# meduza01.net
KiCad netlist of a schematic drawn in EAGLE
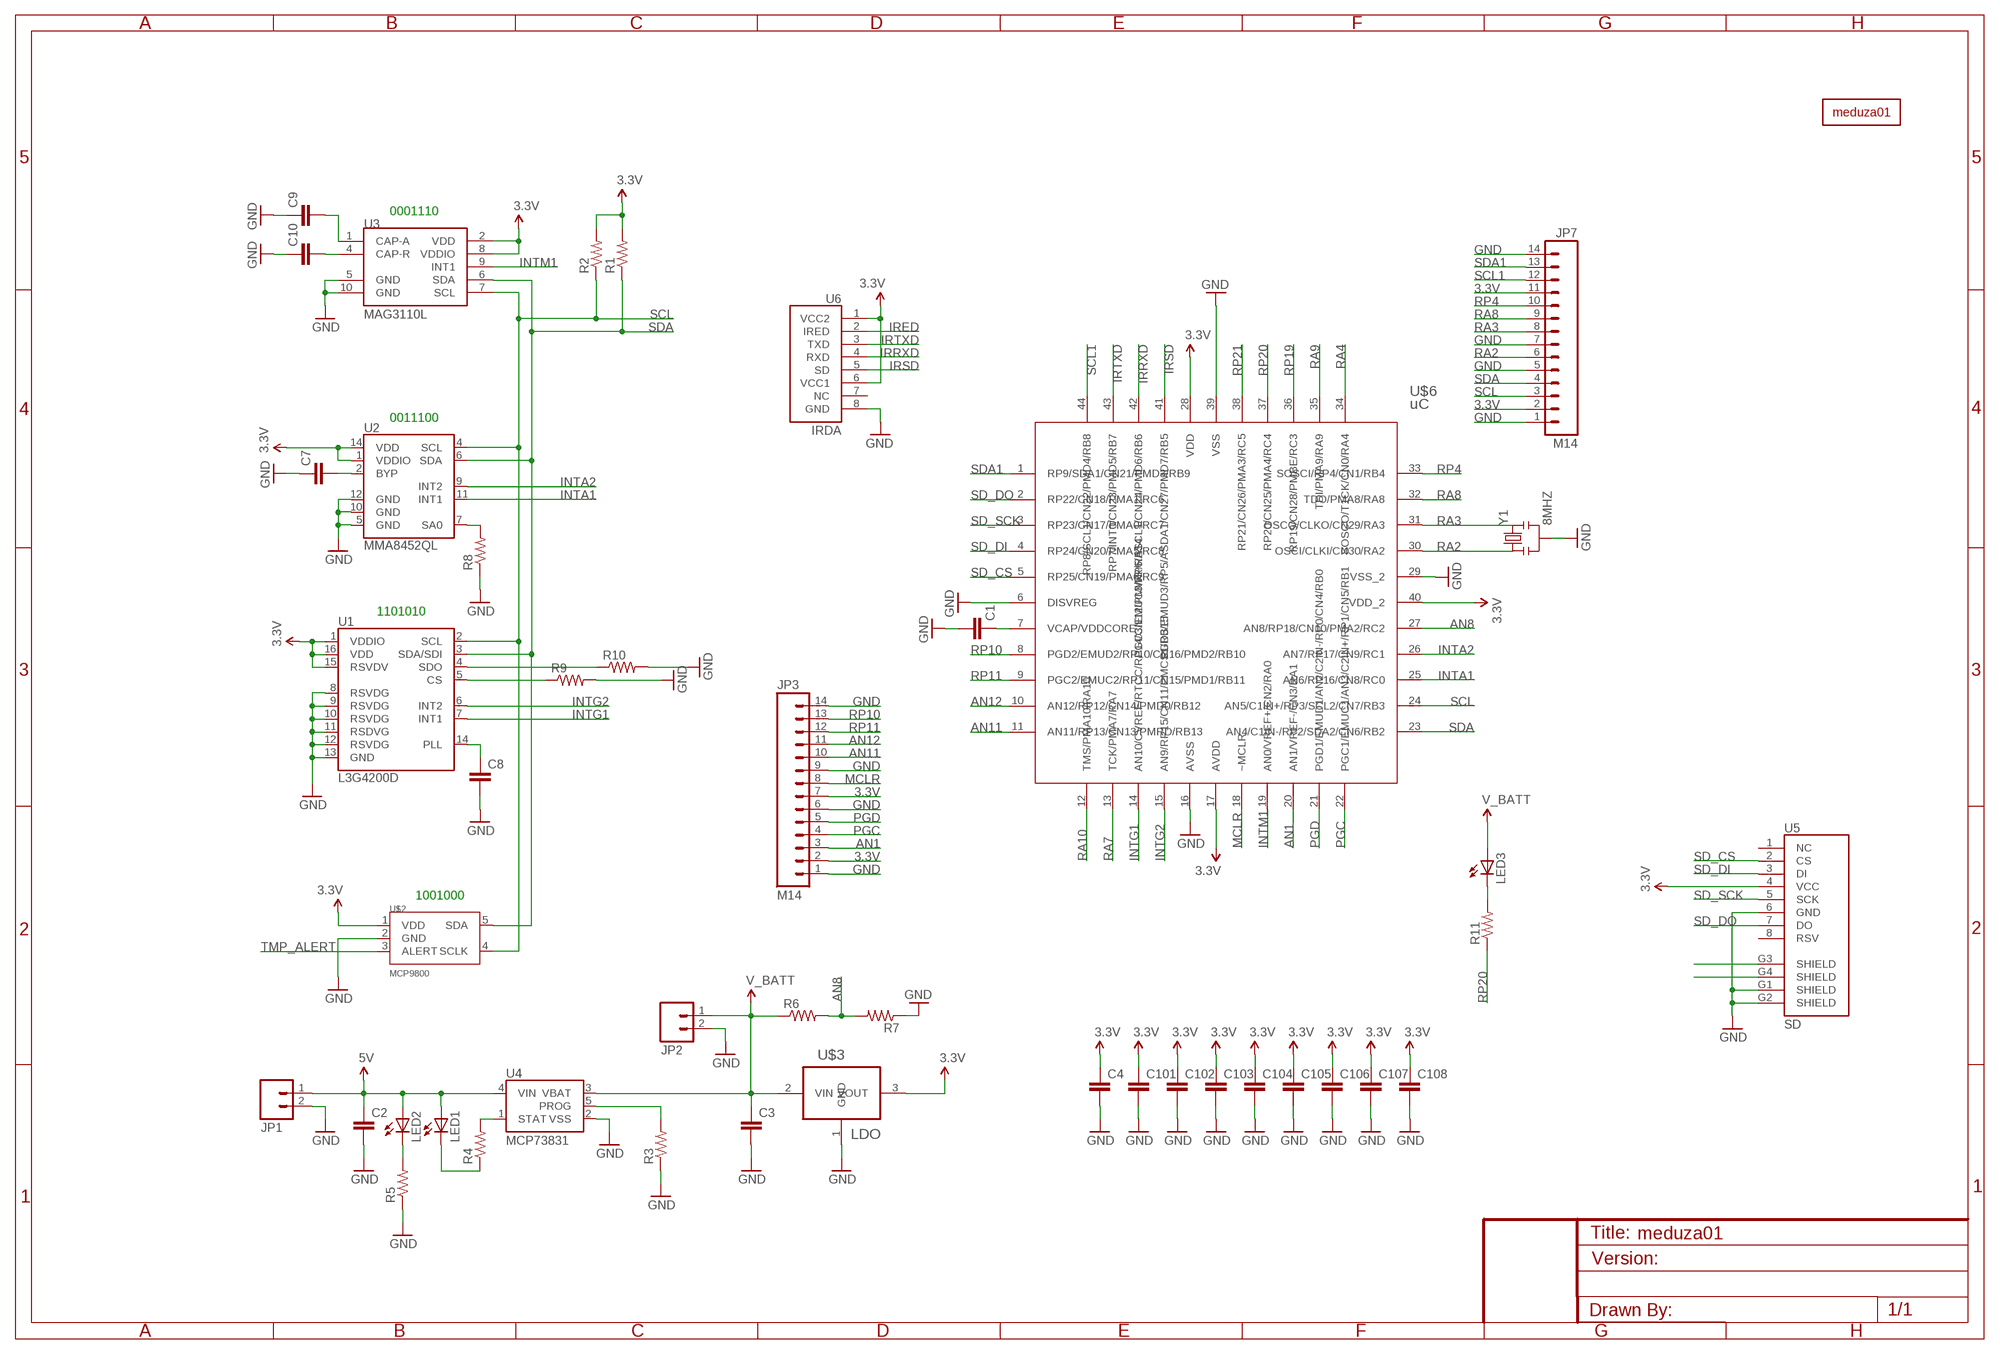
[diagram p0: schematic, sheet 1]

(export (version "E")
  (design (tool "Eeschema 10.0.6"))
  (components
    (comp (ref "C1")
      (value "CAP0603-CAP")
      (footprint "eagle-import:0603-CAP")
      (libsource (lib "eagle-import") (part "CAP0603-CAP"))
    )
    (comp (ref "C2")
      (value "CAP0805")
      (footprint "eagle-import:0805")
      (libsource (lib "eagle-import") (part "SparkFun-Passives_CAP0805"))
    )
    (comp (ref "C3")
      (value "CAP0805")
      (footprint "eagle-import:0805")
      (libsource (lib "eagle-import") (part "SparkFun-Passives_CAP0805"))
    )
    (comp (ref "C4")
      (value "CAP0805")
      (footprint "eagle-import:0805")
      (libsource (lib "eagle-import") (part "SparkFun-Passives_CAP0805"))
    )
    (comp (ref "C7")
      (value "CAP0603-CAP")
      (footprint "eagle-import:0603-CAP")
      (libsource (lib "eagle-import") (part "CAP0603-CAP"))
    )
    (comp (ref "C8")
      (value "CAP0603-CAP")
      (footprint "eagle-import:0603-CAP")
      (libsource (lib "eagle-import") (part "CAP0603-CAP"))
    )
    (comp (ref "C9")
      (value "CAP0603-CAP")
      (footprint "eagle-import:0603-CAP")
      (libsource (lib "eagle-import") (part "CAP0603-CAP"))
    )
    (comp (ref "C10")
      (value "CAP0603-CAP")
      (footprint "eagle-import:0603-CAP")
      (libsource (lib "eagle-import") (part "CAP0603-CAP"))
    )
    (comp (ref "C101")
      (value "CAP0603-CAP")
      (footprint "eagle-import:0603-CAP")
      (libsource (lib "eagle-import") (part "CAP0603-CAP"))
    )
    (comp (ref "C102")
      (value "CAP0603-CAP")
      (footprint "eagle-import:0603-CAP")
      (libsource (lib "eagle-import") (part "CAP0603-CAP"))
    )
    (comp (ref "C103")
      (value "CAP0603-CAP")
      (footprint "eagle-import:0603-CAP")
      (libsource (lib "eagle-import") (part "CAP0603-CAP"))
    )
    (comp (ref "C104")
      (value "CAP0603-CAP")
      (footprint "eagle-import:0603-CAP")
      (libsource (lib "eagle-import") (part "CAP0603-CAP"))
    )
    (comp (ref "C105")
      (value "CAP0603-CAP")
      (footprint "eagle-import:0603-CAP")
      (libsource (lib "eagle-import") (part "CAP0603-CAP"))
    )
    (comp (ref "C106")
      (value "CAP0603-CAP")
      (footprint "eagle-import:0603-CAP")
      (libsource (lib "eagle-import") (part "CAP0603-CAP"))
    )
    (comp (ref "C107")
      (value "CAP0603-CAP")
      (footprint "eagle-import:0603-CAP")
      (libsource (lib "eagle-import") (part "CAP0603-CAP"))
    )
    (comp (ref "C108")
      (value "CAP0603-CAP")
      (footprint "eagle-import:0603-CAP")
      (libsource (lib "eagle-import") (part "CAP0603-CAP"))
    )
    (comp (ref "JP1")
      (value "M02PTH")
      (footprint "eagle-import:1X02")
      (libsource (lib "eagle-import") (part "M02PTH"))
    )
    (comp (ref "JP2")
      (value "M02PTH")
      (footprint "eagle-import:1X02")
      (libsource (lib "eagle-import") (part "M02PTH"))
    )
    (comp (ref "JP3")
      (value "M14")
      (footprint "eagle-import:1X14")
      (libsource (lib "eagle-import") (part "M14"))
    )
    (comp (ref "JP7")
      (value "M14")
      (footprint "eagle-import:1X14")
      (libsource (lib "eagle-import") (part "M14"))
    )
    (comp (ref "LED1")
      (value "LED1206")
      (footprint "eagle-import:LED-1206")
      (libsource (lib "eagle-import") (part "LED1206"))
    )
    (comp (ref "LED2")
      (value "LED1206")
      (footprint "eagle-import:LED-1206")
      (libsource (lib "eagle-import") (part "LED1206"))
    )
    (comp (ref "LED3")
      (value "LED1206")
      (footprint "eagle-import:LED-1206")
      (libsource (lib "eagle-import") (part "LED1206"))
    )
    (comp (ref "R1")
      (value "RESISTOR0603-RES")
      (footprint "eagle-import:0603-RES")
      (libsource (lib "eagle-import") (part "RESISTOR0603-RES"))
    )
    (comp (ref "R2")
      (value "RESISTOR0603-RES")
      (footprint "eagle-import:0603-RES")
      (libsource (lib "eagle-import") (part "RESISTOR0603-RES"))
    )
    (comp (ref "R3")
      (value "RESISTOR0603-RES")
      (footprint "eagle-import:0603-RES")
      (libsource (lib "eagle-import") (part "SparkFun-Resistors_RESISTOR0603-RES"))
    )
    (comp (ref "R4")
      (value "RESISTOR0603-RES")
      (footprint "eagle-import:0603-RES")
      (libsource (lib "eagle-import") (part "SparkFun-Resistors_RESISTOR0603-RES"))
    )
    (comp (ref "R5")
      (value "RESISTOR0603-RES")
      (footprint "eagle-import:0603-RES")
      (libsource (lib "eagle-import") (part "SparkFun-Resistors_RESISTOR0603-RES"))
    )
    (comp (ref "R6")
      (value "RESISTOR0603-RES")
      (footprint "eagle-import:0603-RES")
      (libsource (lib "eagle-import") (part "SparkFun-Resistors_RESISTOR0603-RES"))
    )
    (comp (ref "R7")
      (value "RESISTOR0603-RES")
      (footprint "eagle-import:0603-RES")
      (libsource (lib "eagle-import") (part "SparkFun-Resistors_RESISTOR0603-RES"))
    )
    (comp (ref "R8")
      (value "RESISTOR0603-RES")
      (footprint "eagle-import:0603-RES")
      (libsource (lib "eagle-import") (part "RESISTOR0603-RES"))
    )
    (comp (ref "R9")
      (value "RESISTOR0603-RES")
      (footprint "eagle-import:0603-RES")
      (libsource (lib "eagle-import") (part "RESISTOR0603-RES"))
    )
    (comp (ref "R10")
      (value "RESISTOR0603-RES")
      (footprint "eagle-import:0603-RES")
      (libsource (lib "eagle-import") (part "RESISTOR0603-RES"))
    )
    (comp (ref "R11")
      (value "RESISTOR0603-RES")
      (footprint "eagle-import:0603-RES")
      (libsource (lib "eagle-import") (part "SparkFun-Resistors_RESISTOR0603-RES"))
    )
    (comp (ref "U$1")
      (value "MEDUZA01")
      (footprint "eagle-import:MEDUZA01")
      (libsource (lib "eagle-import") (part "MEDUZA01"))
    )
    (comp (ref "U$2")
      (value "MCP9800")
      (footprint "eagle-import:SOT23-5")
      (libsource (lib "eagle-import") (part "MCP9800"))
    )
    (comp (ref "U$3")
      (value "LDO")
      (footprint "eagle-import:SOT89R")
      (libsource (lib "eagle-import") (part "MCP1700T-3302E/TTSOT89MCP1700-3N"))
    )
    (comp (ref "U$6")
      (value "uC")
      (footprint "eagle-import:QFP80P1200X1200X120-44N")
      (fields (field (name "MPN") "PIC24FJ64GA004-I/PT"))
      (libsource (lib "eagle-import") (part "PIC24FJ64GA004"))
    )
    (comp (ref "U1")
      (value "L3G4200D")
      (footprint "eagle-import:LGA16-4X4")
      (libsource (lib "eagle-import") (part "L3G4200D"))
    )
    (comp (ref "U2")
      (value "MMA8452QL")
      (footprint "eagle-import:QFN-16_0.5MM-EXTRA")
      (libsource (lib "eagle-import") (part "MMA8452QL"))
    )
    (comp (ref "U3")
      (value "MAG3110L")
      (footprint "eagle-import:DFN-10-EXTRA")
      (libsource (lib "eagle-import") (part "MAG3110L"))
    )
    (comp (ref "U4")
      (value "MCP73831")
      (footprint "eagle-import:SOT23-5")
      (libsource (lib "eagle-import") (part "MCP73831"))
    )
    (comp (ref "U5")
      (value "SD")
      (footprint "eagle-import:MOLEX-SD-47309")
      (libsource (lib "eagle-import") (part "USD-SOCKETMOLEX47309"))
    )
    (comp (ref "U6")
      (value "IRDA")
      (footprint "eagle-import:TFDU6300")
      (libsource (lib "eagle-import") (part "TFDU6300TFDU6300"))
    )
    (comp (ref "Y1")
      (value "8MHZ")
      (footprint "eagle-import:RESONATOR-SMD")
      (libsource (lib "eagle-import") (part "RESONATOR8MHZ"))
    )
  )
  (nets
    (net (code "1") (name "/AN1") (class "Default")
      (node (ref "JP3") (pin "3") (pinfunction "3_3") (pintype "passive"))
      (node (ref "U$6") (pin "20") (pinfunction "AN1/VREF-/CN3/RA1_20") (pintype "bidirectional"))
    )
    (net (code "2") (name "/AN8") (class "Default")
      (node (ref "R6") (pin "2") (pinfunction "2_2") (pintype "passive"))
      (node (ref "R7") (pin "2") (pinfunction "2_2") (pintype "passive"))
      (node (ref "U$6") (pin "27") (pinfunction "AN8/RP18/CN10/PMA2/RC2_27") (pintype "bidirectional"))
    )
    (net (code "3") (name "/AN11") (class "Default")
      (node (ref "JP3") (pin "10") (pinfunction "10_10") (pintype "passive"))
      (node (ref "U$6") (pin "11") (pinfunction "AN11/RP13/CN13/PMRD/RB13_11") (pintype "bidirectional"))
    )
    (net (code "4") (name "/AN12") (class "Default")
      (node (ref "JP3") (pin "11") (pinfunction "11_11") (pintype "passive"))
      (node (ref "U$6") (pin "10") (pinfunction "AN12/RP12/CN14/PMD0/RB12_10") (pintype "bidirectional"))
    )
    (net (code "5") (name "/INTA1") (class "Default")
      (node (ref "U$6") (pin "25") (pinfunction "AN6/RP16/CN8/RC0_25") (pintype "bidirectional"))
      (node (ref "U2") (pin "11") (pinfunction "INT1_11") (pintype "bidirectional"))
    )
    (net (code "6") (name "/INTA2") (class "Default")
      (node (ref "U$6") (pin "26") (pinfunction "AN7/RP17/CN9/RC1_26") (pintype "bidirectional"))
      (node (ref "U2") (pin "9") (pinfunction "INT2_9") (pintype "bidirectional"))
    )
    (net (code "7") (name "/INTG1") (class "Default")
      (node (ref "U$6") (pin "14") (pinfunction "AN10/CVREF/RTCC/RP14/CN12/PMWR/RB14_14") (pintype "bidirectional"))
      (node (ref "U1") (pin "7") (pinfunction "INT1_7") (pintype "bidirectional"))
    )
    (net (code "8") (name "/INTG2") (class "Default")
      (node (ref "U$6") (pin "15") (pinfunction "AN9/RP15/CN11/PMCS1/RB15_15") (pintype "bidirectional"))
      (node (ref "U1") (pin "6") (pinfunction "INT2_6") (pintype "bidirectional"))
    )
    (net (code "9") (name "/INTM1") (class "Default")
      (node (ref "U$6") (pin "19") (pinfunction "AN0/VREF+/CN2/RA0_19") (pintype "bidirectional"))
      (node (ref "U3") (pin "9") (pinfunction "INT1_9") (pintype "bidirectional"))
    )
    (net (code "10") (name "/IRED") (class "Default")
      (node (ref "U6") (pin "2") (pinfunction "IRED_2") (pintype "bidirectional"))
    )
    (net (code "11") (name "/IRRXD") (class "Default")
      (node (ref "U$6") (pin "42") (pinfunction "PGC3/EMUC3/RP6/ASCL1/CN24/PMD6/RB6_42") (pintype "bidirectional"))
      (node (ref "U6") (pin "4") (pinfunction "RXD_4") (pintype "bidirectional"))
    )
    (net (code "12") (name "/IRSD") (class "Default")
      (node (ref "U$6") (pin "41") (pinfunction "PGD3/EMUD3/RP5/ASDA1/CN27/PMD7/RB5_41") (pintype "bidirectional"))
      (node (ref "U6") (pin "5") (pinfunction "SD_5") (pintype "bidirectional"))
    )
    (net (code "13") (name "/IRTXD") (class "Default")
      (node (ref "U$6") (pin "43") (pinfunction "RP7/INT0/CN23/PMD5/RB7_43") (pintype "bidirectional"))
      (node (ref "U6") (pin "3") (pinfunction "TXD_3") (pintype "bidirectional"))
    )
    (net (code "14") (name "/MCLR") (class "Default")
      (node (ref "JP3") (pin "8") (pinfunction "8_8") (pintype "passive"))
      (node (ref "U$6") (pin "18") (pinfunction "~{MCLR}_18") (pintype "bidirectional"))
    )
    (net (code "15") (name "/PGC") (class "Default")
      (node (ref "JP3") (pin "4") (pinfunction "4_4") (pintype "passive"))
      (node (ref "U$6") (pin "22") (pinfunction "PGC1/EMUC1/AN3/C2IN+/RP1/CN5/RB1_22") (pintype "bidirectional"))
    )
    (net (code "16") (name "/PGD") (class "Default")
      (node (ref "JP3") (pin "5") (pinfunction "5_5") (pintype "passive"))
      (node (ref "U$6") (pin "21") (pinfunction "PGD1/EMUD1/AN2/C2IN-/RP0/CN4/RB0_21") (pintype "bidirectional"))
    )
    (net (code "17") (name "/RA2") (class "Default")
      (node (ref "JP7") (pin "6") (pinfunction "6_6") (pintype "passive"))
      (node (ref "U$6") (pin "30") (pinfunction "OSCI/CLKI/CN30/RA2_30") (pintype "bidirectional"))
      (node (ref "Y1") (pin "1") (pinfunction "1_1") (pintype "passive"))
    )
    (net (code "18") (name "/RA3") (class "Default")
      (node (ref "JP7") (pin "8") (pinfunction "8_8") (pintype "passive"))
      (node (ref "U$6") (pin "31") (pinfunction "OSCO/CLKO/CN29/RA3_31") (pintype "bidirectional"))
      (node (ref "Y1") (pin "3") (pinfunction "3_3") (pintype "passive"))
    )
    (net (code "19") (name "/RA4") (class "Default")
      (node (ref "U$6") (pin "34") (pinfunction "SOSCO/T1CK/CN0/RA4_34") (pintype "bidirectional"))
    )
    (net (code "20") (name "/RA7") (class "Default")
      (node (ref "U$6") (pin "13") (pinfunction "TCK/PMA7/RA7_13") (pintype "bidirectional"))
    )
    (net (code "21") (name "/RA8") (class "Default")
      (node (ref "JP7") (pin "9") (pinfunction "9_9") (pintype "passive"))
      (node (ref "U$6") (pin "32") (pinfunction "TDO/PMA8/RA8_32") (pintype "bidirectional"))
    )
    (net (code "22") (name "/RA9") (class "Default")
      (node (ref "U$6") (pin "35") (pinfunction "TDI/PMA9/RA9_35") (pintype "bidirectional"))
    )
    (net (code "23") (name "/RA10") (class "Default")
      (node (ref "U$6") (pin "12") (pinfunction "TMS/PMA10/RA10_12") (pintype "bidirectional"))
    )
    (net (code "24") (name "/RP4") (class "Default")
      (node (ref "JP7") (pin "10") (pinfunction "10_10") (pintype "passive"))
      (node (ref "U$6") (pin "33") (pinfunction "SOSCI/RP4/CN1/RB4_33") (pintype "bidirectional"))
    )
    (net (code "25") (name "/RP10") (class "Default")
      (node (ref "JP3") (pin "13") (pinfunction "13_13") (pintype "passive"))
      (node (ref "U$6") (pin "8") (pinfunction "PGD2/EMUD2/RP10/CN16/PMD2/RB10_8") (pintype "bidirectional"))
    )
    (net (code "26") (name "/RP11") (class "Default")
      (node (ref "JP3") (pin "12") (pinfunction "12_12") (pintype "passive"))
      (node (ref "U$6") (pin "9") (pinfunction "PGC2/EMUC2/RP11/CN15/PMD1/RB11_9") (pintype "bidirectional"))
    )
    (net (code "27") (name "/RP19") (class "Default")
      (node (ref "U$6") (pin "36") (pinfunction "RP19/CN28/PMBE/RC3_36") (pintype "bidirectional"))
    )
    (net (code "28") (name "/RP20") (class "Default")
      (node (ref "R11") (pin "1") (pinfunction "1_1") (pintype "passive"))
      (node (ref "U$6") (pin "37") (pinfunction "RP20/CN25/PMA4/RC4_37") (pintype "bidirectional"))
    )
    (net (code "29") (name "/RP21") (class "Default")
      (node (ref "U$6") (pin "38") (pinfunction "RP21/CN26/PMA3/RC5_38") (pintype "bidirectional"))
    )
    (net (code "30") (name "/SCL") (class "Default")
      (node (ref "JP7") (pin "3") (pinfunction "3_3") (pintype "passive"))
      (node (ref "R2") (pin "1") (pinfunction "1_1") (pintype "passive"))
      (node (ref "U$2") (pin "4") (pinfunction "SCLK_4") (pintype "input"))
      (node (ref "U$6") (pin "24") (pinfunction "AN5/C1IN+/RP3/SCL2/CN7/RB3_24") (pintype "bidirectional"))
      (node (ref "U1") (pin "2") (pinfunction "SCL_2") (pintype "bidirectional"))
      (node (ref "U2") (pin "4") (pinfunction "SCL_4") (pintype "bidirectional"))
      (node (ref "U3") (pin "7") (pinfunction "SCL_7") (pintype "bidirectional"))
    )
    (net (code "31") (name "/SCL1") (class "Default")
      (node (ref "JP7") (pin "12") (pinfunction "12_12") (pintype "passive"))
      (node (ref "U$6") (pin "44") (pinfunction "RP8/SCL1/CN22/PMD4/RB8_44") (pintype "bidirectional"))
    )
    (net (code "32") (name "/SDA") (class "Default")
      (node (ref "JP7") (pin "4") (pinfunction "4_4") (pintype "passive"))
      (node (ref "R1") (pin "1") (pinfunction "1_1") (pintype "passive"))
      (node (ref "U$2") (pin "5") (pinfunction "SDA_5") (pintype "bidirectional"))
      (node (ref "U$6") (pin "23") (pinfunction "AN4/C1IN-/RP2/SDA2/CN6/RB2_23") (pintype "bidirectional"))
      (node (ref "U1") (pin "3") (pinfunction "SDA/SDI_3") (pintype "bidirectional"))
      (node (ref "U2") (pin "6") (pinfunction "SDA_6") (pintype "bidirectional"))
      (node (ref "U3") (pin "6") (pinfunction "SDA_6") (pintype "bidirectional"))
    )
    (net (code "33") (name "/SDA1") (class "Default")
      (node (ref "JP7") (pin "13") (pinfunction "13_13") (pintype "passive"))
      (node (ref "U$6") (pin "1") (pinfunction "RP9/SDA1/CN21/PMD3/RB9_1") (pintype "bidirectional"))
    )
    (net (code "34") (name "/SD_CS") (class "Default")
      (node (ref "U$6") (pin "5") (pinfunction "RP25/CN19/PMA6/RC9_5") (pintype "bidirectional"))
      (node (ref "U5") (pin "2") (pinfunction "CS_2") (pintype "bidirectional"))
    )
    (net (code "35") (name "/SD_DI") (class "Default")
      (node (ref "U$6") (pin "4") (pinfunction "RP24/CN20/PMA5/RC8_4") (pintype "bidirectional"))
      (node (ref "U5") (pin "3") (pinfunction "DI_3") (pintype "bidirectional"))
    )
    (net (code "36") (name "/SD_DO") (class "Default")
      (node (ref "U$6") (pin "2") (pinfunction "RP22/CN18/PMA1/RC6_2") (pintype "bidirectional"))
      (node (ref "U5") (pin "7") (pinfunction "DO_7") (pintype "bidirectional"))
    )
    (net (code "37") (name "/SD_SCK") (class "Default")
      (node (ref "U$6") (pin "3") (pinfunction "RP23/CN17/PMA0/RC7_3") (pintype "bidirectional"))
      (node (ref "U5") (pin "5") (pinfunction "SCK_5") (pintype "bidirectional"))
    )
    (net (code "38") (name "/TMP_ALERT") (class "Default")
      (node (ref "U$2") (pin "3") (pinfunction "ALERT_3") (pintype "output"))
    )
    (net (code "39") (name "3.3V") (class "Default")
      (node (ref "C101") (pin "1") (pinfunction "1_1") (pintype "passive"))
      (node (ref "C102") (pin "1") (pinfunction "1_1") (pintype "passive"))
      (node (ref "C103") (pin "1") (pinfunction "1_1") (pintype "passive"))
      (node (ref "C104") (pin "1") (pinfunction "1_1") (pintype "passive"))
      (node (ref "C105") (pin "1") (pinfunction "1_1") (pintype "passive"))
      (node (ref "C106") (pin "1") (pinfunction "1_1") (pintype "passive"))
      (node (ref "C107") (pin "1") (pinfunction "1_1") (pintype "passive"))
      (node (ref "C108") (pin "1") (pinfunction "1_1") (pintype "passive"))
      (node (ref "C4") (pin "1") (pinfunction "1_1") (pintype "passive"))
      (node (ref "JP3") (pin "2") (pinfunction "2_2") (pintype "passive"))
      (node (ref "JP3") (pin "7") (pinfunction "7_7") (pintype "passive"))
      (node (ref "JP7") (pin "11") (pinfunction "11_11") (pintype "passive"))
      (node (ref "JP7") (pin "2") (pinfunction "2_2") (pintype "passive"))
      (node (ref "R1") (pin "2") (pinfunction "2_2") (pintype "passive"))
      (node (ref "R2") (pin "2") (pinfunction "2_2") (pintype "passive"))
      (node (ref "U$2") (pin "1") (pinfunction "VDD_1") (pintype "power_in"))
      (node (ref "U$3") (pin "3") (pinfunction "VOUT_3") (pintype "output"))
      (node (ref "U$6") (pin "17") (pinfunction "AVDD_17") (pintype "power_in"))
      (node (ref "U$6") (pin "28") (pinfunction "VDD_28") (pintype "power_in"))
      (node (ref "U$6") (pin "40") (pinfunction "VDD_2_40") (pintype "power_in"))
      (node (ref "U1") (pin "1") (pinfunction "VDDIO_1") (pintype "bidirectional"))
      (node (ref "U1") (pin "15") (pinfunction "RSVDV_15") (pintype "bidirectional"))
      (node (ref "U1") (pin "16") (pinfunction "VDD_16") (pintype "bidirectional"))
      (node (ref "U2") (pin "1") (pinfunction "VDDIO_1") (pintype "bidirectional"))
      (node (ref "U2") (pin "14") (pinfunction "VDD_14") (pintype "bidirectional"))
      (node (ref "U3") (pin "2") (pinfunction "VDD_2") (pintype "bidirectional"))
      (node (ref "U3") (pin "8") (pinfunction "VDDIO_8") (pintype "bidirectional"))
      (node (ref "U5") (pin "4") (pinfunction "VCC_4") (pintype "bidirectional"))
      (node (ref "U6") (pin "1") (pinfunction "VCC2_1") (pintype "bidirectional"))
      (node (ref "U6") (pin "6") (pinfunction "VCC1_6") (pintype "bidirectional"))
    )
    (net (code "40") (name "5V") (class "Default")
      (node (ref "C2") (pin "1") (pinfunction "1_1") (pintype "passive"))
      (node (ref "JP1") (pin "1") (pinfunction "1_1") (pintype "passive"))
      (node (ref "LED1") (pin "A") (pinfunction "A_A") (pintype "passive"))
      (node (ref "LED2") (pin "A") (pinfunction "A_A") (pintype "passive"))
      (node (ref "U4") (pin "4") (pinfunction "VIN_4") (pintype "power_in"))
    )
    (net (code "41") (name "GND") (class "Default")
      (node (ref "C1") (pin "2") (pinfunction "2_2") (pintype "passive"))
      (node (ref "C10") (pin "1") (pinfunction "1_1") (pintype "passive"))
      (node (ref "C101") (pin "2") (pinfunction "2_2") (pintype "passive"))
      (node (ref "C102") (pin "2") (pinfunction "2_2") (pintype "passive"))
      (node (ref "C103") (pin "2") (pinfunction "2_2") (pintype "passive"))
      (node (ref "C104") (pin "2") (pinfunction "2_2") (pintype "passive"))
      (node (ref "C105") (pin "2") (pinfunction "2_2") (pintype "passive"))
      (node (ref "C106") (pin "2") (pinfunction "2_2") (pintype "passive"))
      (node (ref "C107") (pin "2") (pinfunction "2_2") (pintype "passive"))
      (node (ref "C108") (pin "2") (pinfunction "2_2") (pintype "passive"))
      (node (ref "C2") (pin "2") (pinfunction "2_2") (pintype "passive"))
      (node (ref "C3") (pin "2") (pinfunction "2_2") (pintype "passive"))
      (node (ref "C4") (pin "2") (pinfunction "2_2") (pintype "passive"))
      (node (ref "C7") (pin "1") (pinfunction "1_1") (pintype "passive"))
      (node (ref "C8") (pin "2") (pinfunction "2_2") (pintype "passive"))
      (node (ref "C9") (pin "1") (pinfunction "1_1") (pintype "passive"))
      (node (ref "JP1") (pin "2") (pinfunction "2_2") (pintype "passive"))
      (node (ref "JP2") (pin "2") (pinfunction "2_2") (pintype "passive"))
      (node (ref "JP3") (pin "1") (pinfunction "1_1") (pintype "passive"))
      (node (ref "JP3") (pin "14") (pinfunction "14_14") (pintype "passive"))
      (node (ref "JP3") (pin "6") (pinfunction "6_6") (pintype "passive"))
      (node (ref "JP3") (pin "9") (pinfunction "9_9") (pintype "passive"))
      (node (ref "JP7") (pin "1") (pinfunction "1_1") (pintype "passive"))
      (node (ref "JP7") (pin "14") (pinfunction "14_14") (pintype "passive"))
      (node (ref "JP7") (pin "5") (pinfunction "5_5") (pintype "passive"))
      (node (ref "JP7") (pin "7") (pinfunction "7_7") (pintype "passive"))
      (node (ref "R10") (pin "2") (pinfunction "2_2") (pintype "passive"))
      (node (ref "R3") (pin "1") (pinfunction "1_1") (pintype "passive"))
      (node (ref "R5") (pin "1") (pinfunction "1_1") (pintype "passive"))
      (node (ref "R7") (pin "1") (pinfunction "1_1") (pintype "passive"))
      (node (ref "R8") (pin "1") (pinfunction "1_1") (pintype "passive"))
      (node (ref "R9") (pin "2") (pinfunction "2_2") (pintype "passive"))
      (node (ref "U$2") (pin "2") (pinfunction "GND_2") (pintype "passive"))
      (node (ref "U$3") (pin "1") (pinfunction "GND_1") (pintype "passive"))
      (node (ref "U$6") (pin "16") (pinfunction "AVSS_16") (pintype "power_in"))
      (node (ref "U$6") (pin "29") (pinfunction "VSS_2_29") (pintype "power_in"))
      (node (ref "U$6") (pin "39") (pinfunction "VSS_39") (pintype "power_in"))
      (node (ref "U$6") (pin "6") (pinfunction "DISVREG_6") (pintype "passive"))
      (node (ref "U1") (pin "10") (pinfunction "RSVDG_10") (pintype "bidirectional"))
      (node (ref "U1") (pin "11") (pinfunction "RSDVG_11") (pintype "bidirectional"))
      (node (ref "U1") (pin "12") (pinfunction "RSVDG_12") (pintype "bidirectional"))
      (node (ref "U1") (pin "13") (pinfunction "GND_13") (pintype "bidirectional"))
      (node (ref "U1") (pin "8") (pinfunction "RSVDG_8") (pintype "bidirectional"))
      (node (ref "U1") (pin "9") (pinfunction "RSVDG_9") (pintype "bidirectional"))
      (node (ref "U2") (pin "10") (pinfunction "GND_10") (pintype "bidirectional"))
      (node (ref "U2") (pin "12") (pinfunction "GND_12") (pintype "bidirectional"))
      (node (ref "U2") (pin "5") (pinfunction "GND_5") (pintype "bidirectional"))
      (node (ref "U3") (pin "10") (pinfunction "GND_10") (pintype "bidirectional"))
      (node (ref "U3") (pin "5") (pinfunction "GND_5") (pintype "bidirectional"))
      (node (ref "U4") (pin "2") (pinfunction "VSS_2") (pintype "power_in"))
      (node (ref "U5") (pin "6") (pinfunction "GND_6") (pintype "bidirectional"))
      (node (ref "U5") (pin "G1") (pinfunction "SHIELD_G1") (pintype "bidirectional"))
      (node (ref "U5") (pin "G2") (pinfunction "SHIELD_G2") (pintype "bidirectional"))
      (node (ref "U6") (pin "8") (pinfunction "GND_8") (pintype "bidirectional"))
      (node (ref "Y1") (pin "2") (pinfunction "2_2") (pintype "passive"))
    )
    (net (code "42") (name "Net-(LED1-PadC)") (class "Default")
      (node (ref "LED1") (pin "C") (pinfunction "C_C") (pintype "passive"))
      (node (ref "R4") (pin "1") (pinfunction "1_1") (pintype "passive"))
    )
    (net (code "43") (name "Net-(LED2-PadC)") (class "Default")
      (node (ref "LED2") (pin "C") (pinfunction "C_C") (pintype "passive"))
      (node (ref "R5") (pin "2") (pinfunction "2_2") (pintype "passive"))
    )
    (net (code "44") (name "Net-(LED3-PadC)") (class "Default")
      (node (ref "LED3") (pin "C") (pinfunction "C_C") (pintype "passive"))
      (node (ref "R11") (pin "2") (pinfunction "2_2") (pintype "passive"))
    )
    (net (code "45") (name "Net-(U$6-VCAP{slash}VDDCORE)") (class "Default")
      (node (ref "C1") (pin "1") (pinfunction "1_1") (pintype "passive"))
      (node (ref "U$6") (pin "7") (pinfunction "VCAP/VDDCORE_7") (pintype "power_in"))
    )
    (net (code "46") (name "Net-(U1-CS)") (class "Default")
      (node (ref "R9") (pin "1") (pinfunction "1_1") (pintype "passive"))
      (node (ref "U1") (pin "5") (pinfunction "CS_5") (pintype "bidirectional"))
    )
    (net (code "47") (name "Net-(U1-PLL)") (class "Default")
      (node (ref "C8") (pin "1") (pinfunction "1_1") (pintype "passive"))
      (node (ref "U1") (pin "14") (pinfunction "PLL_14") (pintype "bidirectional"))
    )
    (net (code "48") (name "Net-(U1-SDO)") (class "Default")
      (node (ref "R10") (pin "1") (pinfunction "1_1") (pintype "passive"))
      (node (ref "U1") (pin "4") (pinfunction "SDO_4") (pintype "bidirectional"))
    )
    (net (code "49") (name "Net-(U2-BYP)") (class "Default")
      (node (ref "C7") (pin "2") (pinfunction "2_2") (pintype "passive"))
      (node (ref "U2") (pin "2") (pinfunction "BYP_2") (pintype "bidirectional"))
    )
    (net (code "50") (name "Net-(U2-SA0)") (class "Default")
      (node (ref "R8") (pin "2") (pinfunction "2_2") (pintype "passive"))
      (node (ref "U2") (pin "7") (pinfunction "SA0_7") (pintype "bidirectional"))
    )
    (net (code "51") (name "Net-(U3-CAP-A)") (class "Default")
      (node (ref "C9") (pin "2") (pinfunction "2_2") (pintype "passive"))
      (node (ref "U3") (pin "1") (pinfunction "CAP-A_1") (pintype "bidirectional"))
    )
    (net (code "52") (name "Net-(U3-CAP-R)") (class "Default")
      (node (ref "C10") (pin "2") (pinfunction "2_2") (pintype "passive"))
      (node (ref "U3") (pin "4") (pinfunction "CAP-R_4") (pintype "bidirectional"))
    )
    (net (code "53") (name "Net-(U4-PROG)") (class "Default")
      (node (ref "R3") (pin "2") (pinfunction "2_2") (pintype "passive"))
      (node (ref "U4") (pin "5") (pinfunction "PROG_5") (pintype "input"))
    )
    (net (code "54") (name "Net-(U4-STAT)") (class "Default")
      (node (ref "R4") (pin "2") (pinfunction "2_2") (pintype "passive"))
      (node (ref "U4") (pin "1") (pinfunction "STAT_1") (pintype "output"))
    )
    (net (code "55") (name "V_BATT") (class "Default")
      (node (ref "C3") (pin "1") (pinfunction "1_1") (pintype "passive"))
      (node (ref "JP2") (pin "1") (pinfunction "1_1") (pintype "passive"))
      (node (ref "LED3") (pin "A") (pinfunction "A_A") (pintype "passive"))
      (node (ref "R6") (pin "1") (pinfunction "1_1") (pintype "passive"))
      (node (ref "U$3") (pin "2") (pinfunction "VIN_2") (pintype "input"))
      (node (ref "U4") (pin "3") (pinfunction "VBAT_3") (pintype "power_in"))
    )
    (net (code "56") (name "unconnected-(U5-NC-Pad1)") (class "Default")
      (node (ref "U5") (pin "1") (pinfunction "NC_1") (pintype "bidirectional"))
    )
    (net (code "57") (name "unconnected-(U5-RSV-Pad8)") (class "Default")
      (node (ref "U5") (pin "8") (pinfunction "RSV_8") (pintype "bidirectional"))
    )
    (net (code "58") (name "unconnected-(U5-SHIELD-PadG3)") (class "Default")
      (node (ref "U5") (pin "G3") (pinfunction "SHIELD_G3") (pintype "bidirectional"))
    )
    (net (code "59") (name "unconnected-(U5-SHIELD-PadG4)") (class "Default")
      (node (ref "U5") (pin "G4") (pinfunction "SHIELD_G4") (pintype "bidirectional"))
    )
    (net (code "60") (name "unconnected-(U6-NC-Pad7)") (class "Default")
      (node (ref "U6") (pin "7") (pinfunction "NC_7") (pintype "bidirectional"))
    )
  )
)
